# DRV8873.net
KiCad netlist of a schematic drawn in Altium Designer
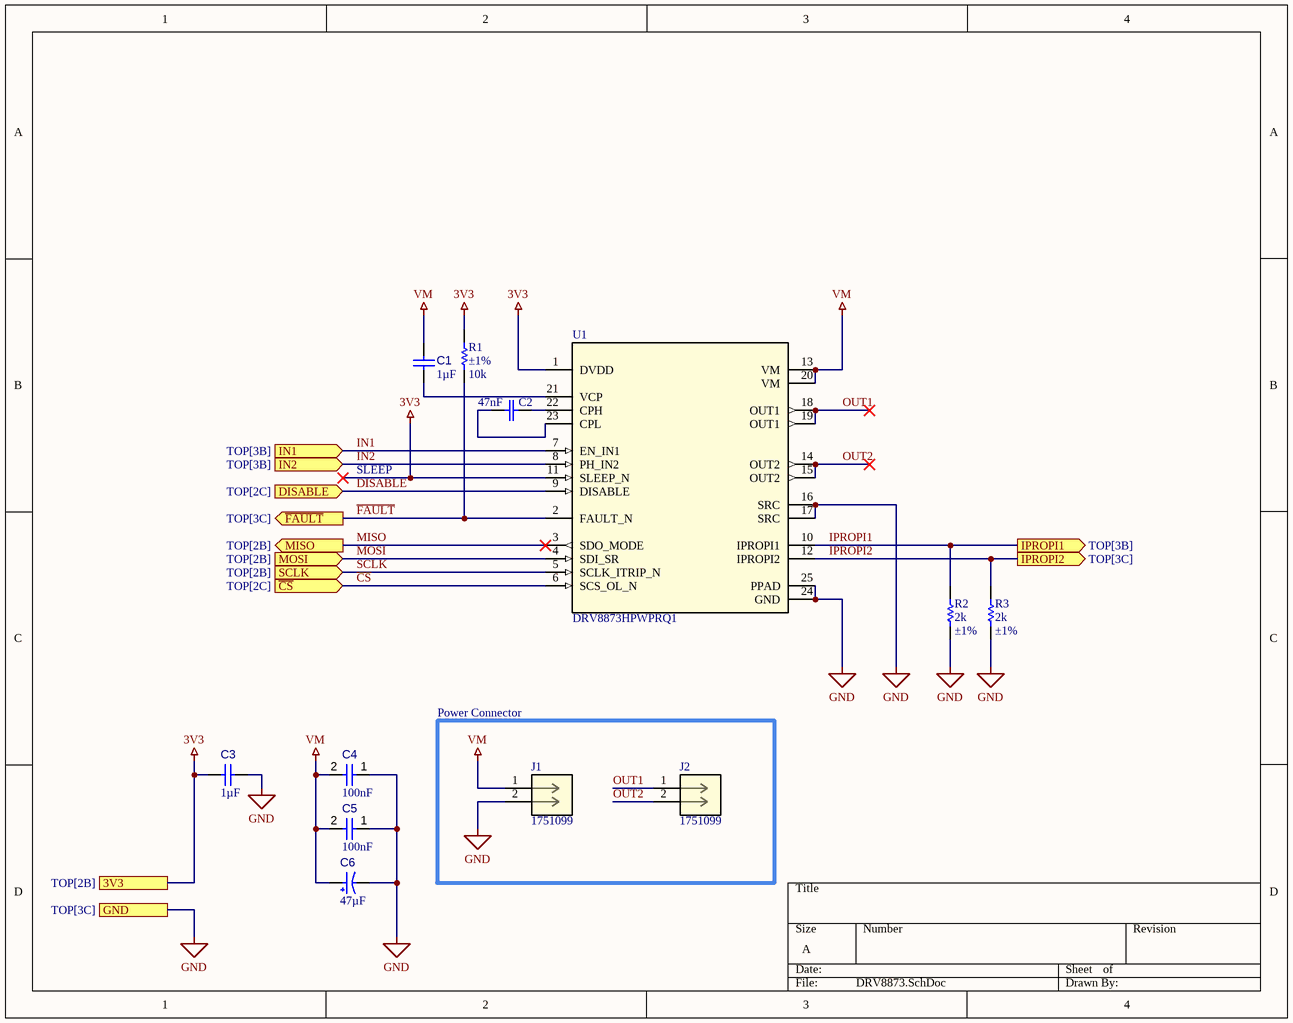
[diagram p0: DRV8873.SchDoc]

(export (version "E")
  (design (tool "Eeschema 10.0.6"))
  (components
    (comp (ref "C1")
      (value "1µF")
      (footprint "CAPC1608X94X35NL15T15")
      (description "Chip Capacitor, 1 uF, +/- 10%, 16 V, 0603 (1608 Metric)")
      (fields (field (name "TOLERANCE") "10%") (field (name "Comment") "Capacitor 1 uF +/- 10% 16 V 0603"))
      (libsource (lib "Altium Default Library") (part "CAP-NP-2"))
    )
    (comp (ref "C2")
      (value "47nF")
      (footprint "CAPC220145_90N_KEM")
      (description "No Description Available")
      (libsource (lib "Altium Default Library") (part "C0805C473K5RACTU"))
    )
    (comp (ref "C3")
      (value "1µF")
      (footprint "CAPC1608X94X35NL15T15")
      (description "Chip Capacitor, 1 uF, +/- 10%, 16 V, 0603 (1608 Metric)")
      (fields (field (name "TOLERANCE") "10%") (field (name "Comment") "Capacitor 1 uF +/- 10% 16 V 0603"))
      (libsource (lib "Altium Default Library") (part "CAP-NP-2"))
    )
    (comp (ref "C4")
      (value "100nF")
      (footprint "CAPC1608X90X40NL10T20")
      (description "Chip Capacitor, 100 nF, +/- 10%, 50 V, 0603 (1608 Metric)")
      (fields (field (name "TOLERANCE") "10%") (field (name "Comment") "Capacitor 100 nF +/-10% 50 V 0603"))
      (libsource (lib "") (part "CAP-NP-2_1"))
    )
    (comp (ref "C5")
      (value "100nF")
      (footprint "CAPC1608X90X40NL10T20")
      (description "Chip Capacitor, 100 nF, +/- 10%, 50 V, 0603 (1608 Metric)")
      (fields (field (name "TOLERANCE") "10%") (field (name "Comment") "Capacitor 100 nF +/-10% 50 V 0603"))
      (libsource (lib "") (part "CAP-NP-2_1"))
    )
    (comp (ref "C6")
      (value "47µF")
      (footprint "CAPPR55-250-1120X630X1220")
      (description "Aluminum Electrolytic Capacitor, 47 uF, +/-20%, 50 V, -40 to 85 degC, 2-Pin THD, RoHS, Bulk")
      (fields (field (name "TOLERANCE") "20%") (field (name "MANUFACTURER") "Panasonic"))
      (libsource (lib "Altium Default Library") (part "CAP-P-2"))
    )
    (comp (ref "J1")
      (value "1751099")
      (footprint "CONN_1751099_PXC")
      (description "No Description Available")
      (libsource (lib "Altium Default Library") (part "1751099"))
    )
    (comp (ref "J2")
      (value "1751099")
      (footprint "CONN_1751099_PXC")
      (description "No Description Available")
      (libsource (lib "Altium Default Library") (part "1751099"))
    )
    (comp (ref "R1")
      (value "~")
      (footprint "RESC0603L")
      (description "RES SMD 10K OHM 1% 1/10W 0603")
      (fields
        (field (name "TOLERANCE") "±1%")
        (field (name "MANUFACTURER") "Vishay Dale")
        (field (name "RESISTANCE") "10k")
        (field (name "MANUFACTURER PART NUMBER") "CRCW060310K0FKEA")
      )
      (libsource (lib "FUTEK Advanced Sensor Technology, Inc") (part "Resistor"))
    )
    (comp (ref "R2")
      (value "ERJ-P06F2001V")
      (footprint "RESC0805L")
      (description "RES SMD 2K OHM 1% 1/2W 0805")
      (fields
        (field (name "MANUFACTURER") "Panasonic Electronic Components")
        (field (name "RESISTANCE") "2k")
        (field (name "TOLERANCE") "±1%")
      )
      (libsource (lib "FUTEK Advanced Sensor Technology, Inc") (part "Resistor"))
    )
    (comp (ref "R3")
      (value "ERJ-P06F2001V")
      (footprint "RESC0805L")
      (description "RES SMD 2K OHM 1% 1/2W 0805")
      (fields
        (field (name "MANUFACTURER") "Panasonic Electronic Components")
        (field (name "RESISTANCE") "2k")
        (field (name "TOLERANCE") "±1%")
      )
      (libsource (lib "FUTEK Advanced Sensor Technology, Inc") (part "Resistor"))
    )
    (comp (ref "U1")
      (value "DRV8873HPWPRQ1")
      (footprint "PWP0024J_N")
      (description "No Description Available")
      (libsource (lib "Altium Default Library") (part "DRV8873HPWPRQ1"))
    )
  )
  (nets
    (net (code "1") (name "/DISABLE") (class "Default")
      (node (ref "U1") (pin "9") (pinfunction "DISABLE_9") (pintype "input"))
    )
    (net (code "2") (name "/IN1") (class "Default")
      (node (ref "U1") (pin "7") (pinfunction "EN_IN1_7") (pintype "input"))
    )
    (net (code "3") (name "/IN2") (class "Default")
      (node (ref "U1") (pin "8") (pinfunction "PH_IN2_8") (pintype "input"))
    )
    (net (code "4") (name "/IPROPI1") (class "Default")
      (node (ref "R2") (pin "2") (pinfunction "2_2") (pintype "passive"))
      (node (ref "U1") (pin "10") (pinfunction "IPROPI1_10") (pintype "passive"))
    )
    (net (code "5") (name "/IPROPI2") (class "Default")
      (node (ref "R3") (pin "2") (pinfunction "2_2") (pintype "passive"))
      (node (ref "U1") (pin "12") (pinfunction "IPROPI2_12") (pintype "passive"))
    )
    (net (code "6") (name "/MISO") (class "Default")
      (node (ref "U1") (pin "3") (pinfunction "SDO_MODE_3") (pintype "output+no_connect"))
    )
    (net (code "7") (name "/MOSI") (class "Default")
      (node (ref "U1") (pin "4") (pinfunction "SDI_SR_4") (pintype "input"))
    )
    (net (code "8") (name "/OUT1") (class "Default")
      (node (ref "J2") (pin "1") (pinfunction "1_1") (pintype "passive"))
      (node (ref "U1") (pin "18") (pinfunction "OUT1_18") (pintype "output"))
      (node (ref "U1") (pin "19") (pinfunction "OUT1_19") (pintype "output"))
    )
    (net (code "9") (name "/OUT2") (class "Default")
      (node (ref "J2") (pin "2") (pinfunction "2_2") (pintype "passive"))
      (node (ref "U1") (pin "14") (pinfunction "OUT2_14") (pintype "output"))
      (node (ref "U1") (pin "15") (pinfunction "OUT2_15") (pintype "output"))
    )
    (net (code "10") (name "/SCLK") (class "Default")
      (node (ref "U1") (pin "5") (pinfunction "SCLK_ITRIP_N_5") (pintype "input"))
    )
    (net (code "11") (name "/~{CS}") (class "Default")
      (node (ref "U1") (pin "6") (pinfunction "SCS_OL_N_6") (pintype "input"))
    )
    (net (code "12") (name "/~{FAULT}") (class "Default")
      (node (ref "R1") (pin "1") (pinfunction "1_1") (pintype "passive"))
      (node (ref "U1") (pin "2") (pinfunction "FAULT_N_2") (pintype "open_collector"))
    )
    (net (code "13") (name "3V3") (class "Default")
      (node (ref "C3") (pin "2") (pinfunction "2_2") (pintype "passive"))
      (node (ref "R1") (pin "2") (pinfunction "2_2") (pintype "passive"))
      (node (ref "U1") (pin "1") (pinfunction "DVDD_1") (pintype "power_in"))
      (node (ref "U1") (pin "11") (pinfunction "SLEEP_N_11") (pintype "input"))
    )
    (net (code "14") (name "GND") (class "Default")
      (node (ref "C3") (pin "1") (pinfunction "1_1") (pintype "passive"))
      (node (ref "C4") (pin "1") (pinfunction "1_1") (pintype "passive"))
      (node (ref "C5") (pin "1") (pinfunction "1_1") (pintype "passive"))
      (node (ref "C6") (pin "2") (pinfunction "2_2") (pintype "passive"))
      (node (ref "J1") (pin "2") (pinfunction "2_2") (pintype "passive"))
      (node (ref "R2") (pin "1") (pinfunction "1_1") (pintype "passive"))
      (node (ref "R3") (pin "1") (pinfunction "1_1") (pintype "passive"))
      (node (ref "U1") (pin "16") (pinfunction "SRC_16") (pintype "passive"))
      (node (ref "U1") (pin "17") (pinfunction "SRC_17") (pintype "passive"))
      (node (ref "U1") (pin "24") (pinfunction "GND_24") (pintype "power_in"))
      (node (ref "U1") (pin "25") (pinfunction "PPAD_25") (pintype "power_in"))
    )
    (net (code "15") (name "Net-(U1-CPH)") (class "Default")
      (node (ref "C2") (pin "2") (pinfunction "2_2") (pintype "passive"))
      (node (ref "U1") (pin "22") (pinfunction "CPH_22") (pintype "power_in"))
    )
    (net (code "16") (name "Net-(U1-CPL)") (class "Default")
      (node (ref "C2") (pin "1") (pinfunction "1_1") (pintype "passive"))
      (node (ref "U1") (pin "23") (pinfunction "CPL_23") (pintype "power_in"))
    )
    (net (code "17") (name "Net-(U1-VCP)") (class "Default")
      (node (ref "C1") (pin "1") (pinfunction "1_1") (pintype "passive"))
      (node (ref "U1") (pin "21") (pinfunction "VCP_21") (pintype "power_in"))
    )
    (net (code "18") (name "VM") (class "Default")
      (node (ref "C1") (pin "2") (pinfunction "2_2") (pintype "passive"))
      (node (ref "C4") (pin "2") (pinfunction "2_2") (pintype "passive"))
      (node (ref "C5") (pin "2") (pinfunction "2_2") (pintype "passive"))
      (node (ref "C6") (pin "1") (pinfunction "1_1") (pintype "passive"))
      (node (ref "J1") (pin "1") (pinfunction "1_1") (pintype "passive"))
      (node (ref "U1") (pin "13") (pinfunction "VM_13") (pintype "power_in"))
      (node (ref "U1") (pin "20") (pinfunction "VM_20") (pintype "power_in"))
    )
  )
)
